# FPGA.net
KiCad netlist of a schematic drawn in Altium Designer
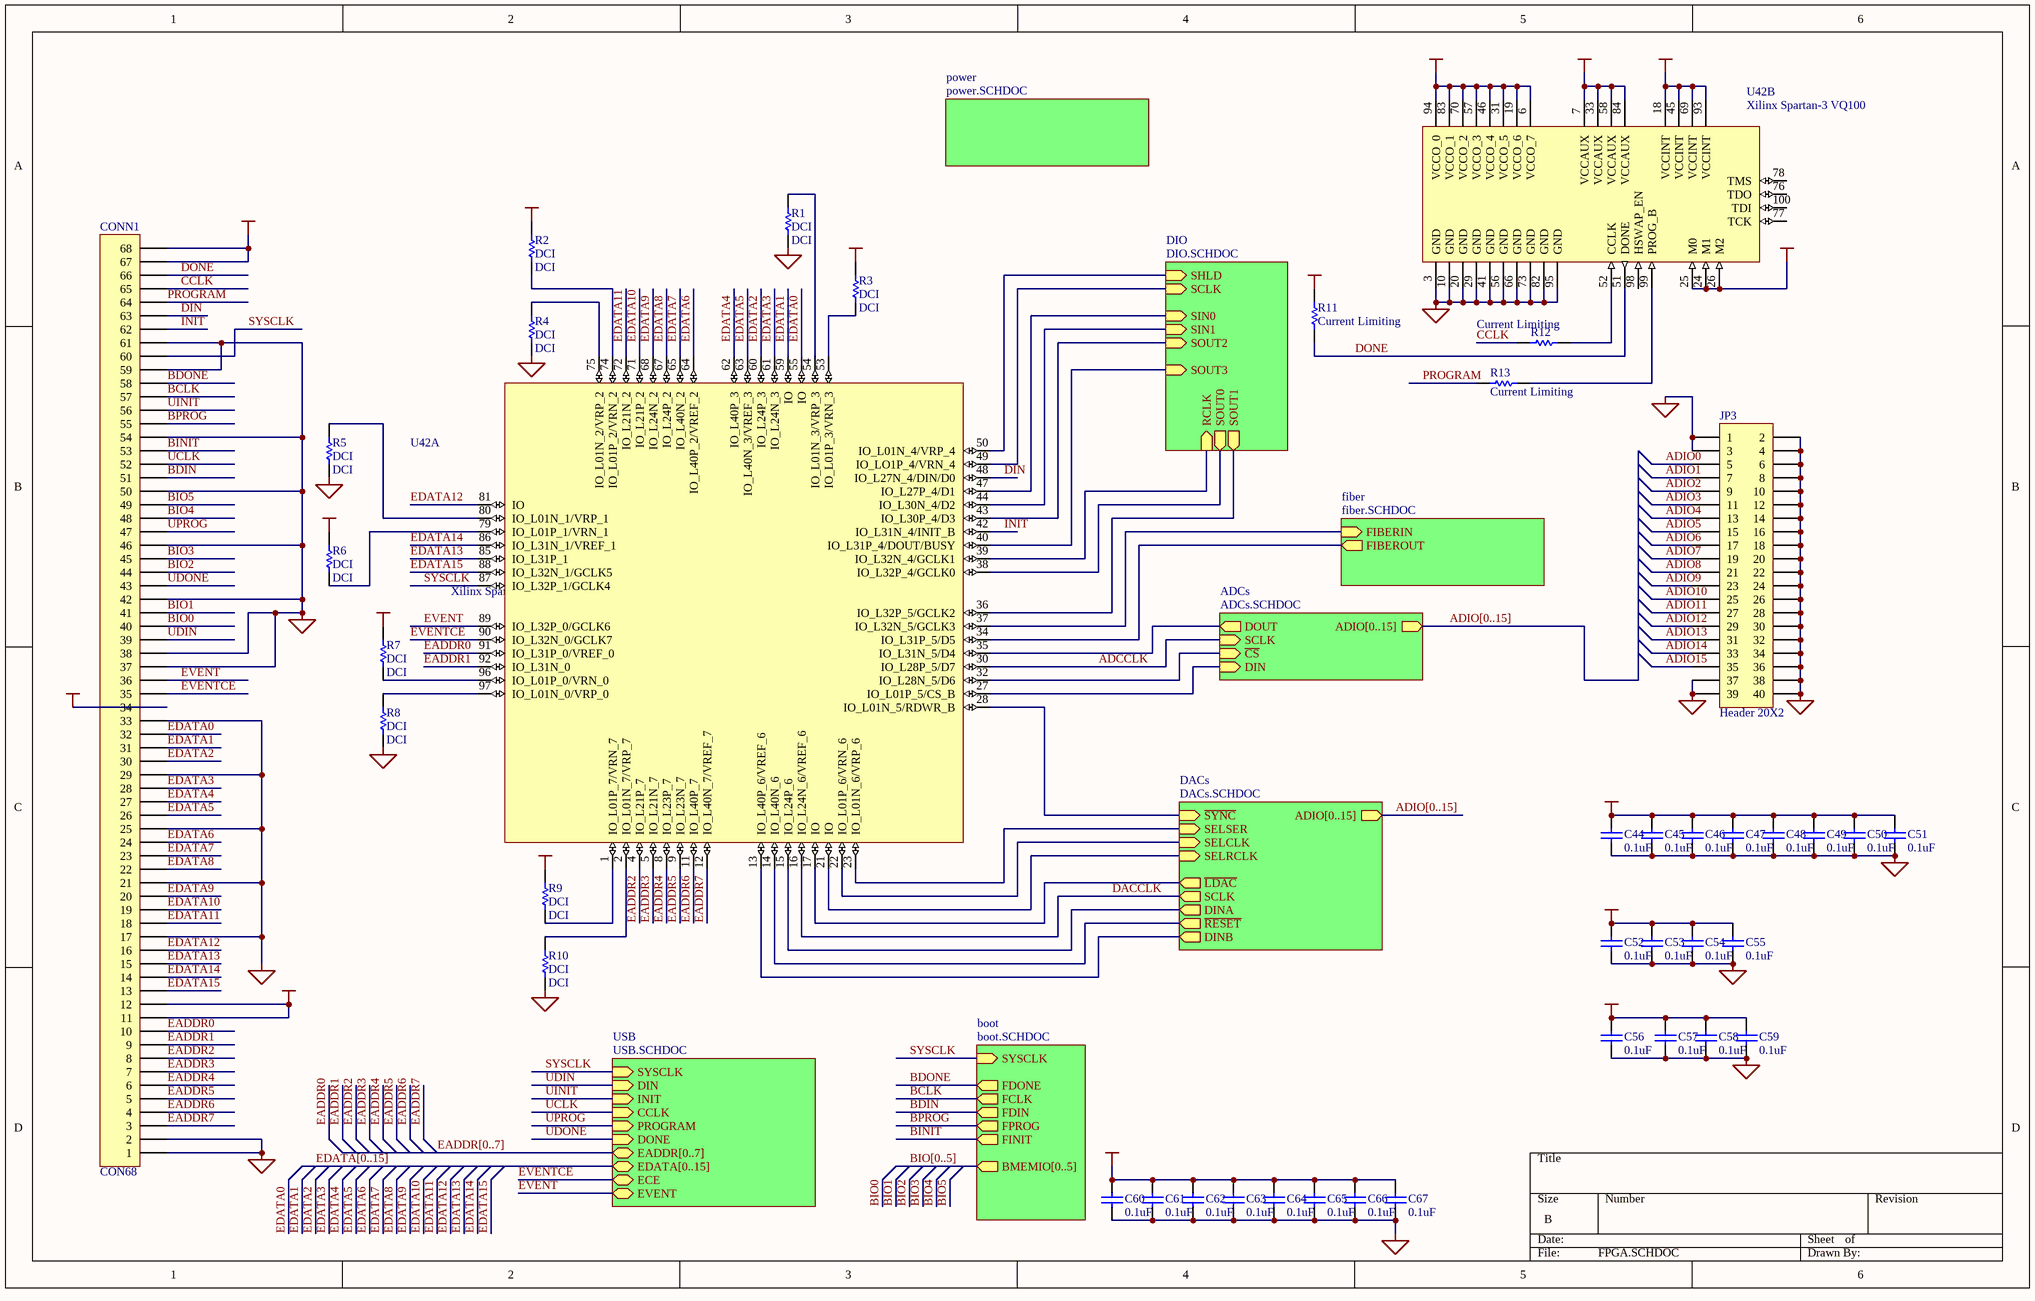
[diagram p0: FPGA.SCHDOC]

(export (version "E")
  (design (tool "Eeschema 10.0.6"))
  (components
    (comp (ref "C44")
      (value "Cap")
      (footprint "CC1608-0603")
      (description "Capacitor")
      (fields
        (field (name "MANUFACTURER") "Generic Components")
        (field (name "ALTIUM_VALUE") "0.1uF")
        (field (name "PUBLISHER") "Altium Limited")
      )
      (libsource (lib "Miscellaneous Devices") (part "Cap"))
    )
    (comp (ref "C45")
      (value "Cap")
      (footprint "CC1608-0603")
      (description "Capacitor")
      (fields
        (field (name "MANUFACTURER") "Generic Components")
        (field (name "ALTIUM_VALUE") "0.1uF")
        (field (name "PUBLISHER") "Altium Limited")
      )
      (libsource (lib "Miscellaneous Devices") (part "Cap"))
    )
    (comp (ref "C46")
      (value "Cap")
      (footprint "CC1608-0603")
      (description "Capacitor")
      (fields
        (field (name "MANUFACTURER") "Generic Components")
        (field (name "ALTIUM_VALUE") "0.1uF")
        (field (name "PUBLISHER") "Altium Limited")
      )
      (libsource (lib "Miscellaneous Devices") (part "Cap"))
    )
    (comp (ref "C47")
      (value "Cap")
      (footprint "CC1608-0603")
      (description "Capacitor")
      (fields
        (field (name "MANUFACTURER") "Generic Components")
        (field (name "ALTIUM_VALUE") "0.1uF")
        (field (name "PUBLISHER") "Altium Limited")
      )
      (libsource (lib "Miscellaneous Devices") (part "Cap"))
    )
    (comp (ref "C48")
      (value "Cap")
      (footprint "CC1608-0603")
      (description "Capacitor")
      (fields
        (field (name "MANUFACTURER") "Generic Components")
        (field (name "ALTIUM_VALUE") "0.1uF")
        (field (name "PUBLISHER") "Altium Limited")
      )
      (libsource (lib "Miscellaneous Devices") (part "Cap"))
    )
    (comp (ref "C49")
      (value "Cap")
      (footprint "CC1608-0603")
      (description "Capacitor")
      (fields
        (field (name "MANUFACTURER") "Generic Components")
        (field (name "ALTIUM_VALUE") "0.1uF")
        (field (name "PUBLISHER") "Altium Limited")
      )
      (libsource (lib "Miscellaneous Devices") (part "Cap"))
    )
    (comp (ref "C50")
      (value "Cap")
      (footprint "CC1608-0603")
      (description "Capacitor")
      (fields
        (field (name "MANUFACTURER") "Generic Components")
        (field (name "ALTIUM_VALUE") "0.1uF")
        (field (name "PUBLISHER") "Altium Limited")
      )
      (libsource (lib "Miscellaneous Devices") (part "Cap"))
    )
    (comp (ref "C51")
      (value "Cap")
      (footprint "CC1608-0603")
      (description "Capacitor")
      (fields
        (field (name "MANUFACTURER") "Generic Components")
        (field (name "ALTIUM_VALUE") "0.1uF")
        (field (name "PUBLISHER") "Altium Limited")
      )
      (libsource (lib "Miscellaneous Devices") (part "Cap"))
    )
    (comp (ref "C52")
      (value "Cap")
      (footprint "CC1608-0603")
      (description "Capacitor")
      (fields
        (field (name "MANUFACTURER") "Generic Components")
        (field (name "ALTIUM_VALUE") "0.1uF")
        (field (name "PUBLISHER") "Altium Limited")
      )
      (libsource (lib "Miscellaneous Devices") (part "Cap"))
    )
    (comp (ref "C53")
      (value "Cap")
      (footprint "CC1608-0603")
      (description "Capacitor")
      (fields
        (field (name "MANUFACTURER") "Generic Components")
        (field (name "ALTIUM_VALUE") "0.1uF")
        (field (name "PUBLISHER") "Altium Limited")
      )
      (libsource (lib "Miscellaneous Devices") (part "Cap"))
    )
    (comp (ref "C54")
      (value "Cap")
      (footprint "CC1608-0603")
      (description "Capacitor")
      (fields
        (field (name "MANUFACTURER") "Generic Components")
        (field (name "ALTIUM_VALUE") "0.1uF")
        (field (name "PUBLISHER") "Altium Limited")
      )
      (libsource (lib "Miscellaneous Devices") (part "Cap"))
    )
    (comp (ref "C55")
      (value "Cap")
      (footprint "CC1608-0603")
      (description "Capacitor")
      (fields
        (field (name "MANUFACTURER") "Generic Components")
        (field (name "ALTIUM_VALUE") "0.1uF")
        (field (name "PUBLISHER") "Altium Limited")
      )
      (libsource (lib "Miscellaneous Devices") (part "Cap"))
    )
    (comp (ref "C56")
      (value "Cap")
      (footprint "CC1608-0603")
      (description "Capacitor")
      (fields
        (field (name "MANUFACTURER") "Generic Components")
        (field (name "ALTIUM_VALUE") "0.1uF")
        (field (name "PUBLISHER") "Altium Limited")
      )
      (libsource (lib "Miscellaneous Devices") (part "Cap"))
    )
    (comp (ref "C57")
      (value "Cap")
      (footprint "CC1608-0603")
      (description "Capacitor")
      (fields
        (field (name "MANUFACTURER") "Generic Components")
        (field (name "ALTIUM_VALUE") "0.1uF")
        (field (name "PUBLISHER") "Altium Limited")
      )
      (libsource (lib "Miscellaneous Devices") (part "Cap"))
    )
    (comp (ref "C58")
      (value "Cap")
      (footprint "CC1608-0603")
      (description "Capacitor")
      (fields
        (field (name "MANUFACTURER") "Generic Components")
        (field (name "ALTIUM_VALUE") "0.1uF")
        (field (name "PUBLISHER") "Altium Limited")
      )
      (libsource (lib "Miscellaneous Devices") (part "Cap"))
    )
    (comp (ref "C59")
      (value "Cap")
      (footprint "CC1608-0603")
      (description "Capacitor")
      (fields
        (field (name "MANUFACTURER") "Generic Components")
        (field (name "ALTIUM_VALUE") "0.1uF")
        (field (name "PUBLISHER") "Altium Limited")
      )
      (libsource (lib "Miscellaneous Devices") (part "Cap"))
    )
    (comp (ref "C60")
      (value "Cap")
      (footprint "CC1608-0603")
      (description "Capacitor")
      (fields
        (field (name "MANUFACTURER") "Generic Components")
        (field (name "ALTIUM_VALUE") "0.1uF")
        (field (name "PUBLISHER") "Altium Limited")
      )
      (libsource (lib "Miscellaneous Devices") (part "Cap"))
    )
    (comp (ref "C61")
      (value "Cap")
      (footprint "CC1608-0603")
      (description "Capacitor")
      (fields
        (field (name "MANUFACTURER") "Generic Components")
        (field (name "ALTIUM_VALUE") "0.1uF")
        (field (name "PUBLISHER") "Altium Limited")
      )
      (libsource (lib "Miscellaneous Devices") (part "Cap"))
    )
    (comp (ref "C62")
      (value "Cap")
      (footprint "CC1608-0603")
      (description "Capacitor")
      (fields
        (field (name "MANUFACTURER") "Generic Components")
        (field (name "ALTIUM_VALUE") "0.1uF")
        (field (name "PUBLISHER") "Altium Limited")
      )
      (libsource (lib "Miscellaneous Devices") (part "Cap"))
    )
    (comp (ref "C63")
      (value "Cap")
      (footprint "CC1608-0603")
      (description "Capacitor")
      (fields
        (field (name "MANUFACTURER") "Generic Components")
        (field (name "ALTIUM_VALUE") "0.1uF")
        (field (name "PUBLISHER") "Altium Limited")
      )
      (libsource (lib "Miscellaneous Devices") (part "Cap"))
    )
    (comp (ref "C64")
      (value "Cap")
      (footprint "CC1608-0603")
      (description "Capacitor")
      (fields
        (field (name "MANUFACTURER") "Generic Components")
        (field (name "ALTIUM_VALUE") "0.1uF")
        (field (name "PUBLISHER") "Altium Limited")
      )
      (libsource (lib "Miscellaneous Devices") (part "Cap"))
    )
    (comp (ref "C65")
      (value "Cap")
      (footprint "CC1608-0603")
      (description "Capacitor")
      (fields
        (field (name "MANUFACTURER") "Generic Components")
        (field (name "ALTIUM_VALUE") "0.1uF")
        (field (name "PUBLISHER") "Altium Limited")
      )
      (libsource (lib "Miscellaneous Devices") (part "Cap"))
    )
    (comp (ref "C66")
      (value "Cap")
      (footprint "CC1608-0603")
      (description "Capacitor")
      (fields
        (field (name "MANUFACTURER") "Generic Components")
        (field (name "ALTIUM_VALUE") "0.1uF")
        (field (name "PUBLISHER") "Altium Limited")
      )
      (libsource (lib "Miscellaneous Devices") (part "Cap"))
    )
    (comp (ref "C67")
      (value "Cap")
      (footprint "CC1608-0603")
      (description "Capacitor")
      (fields
        (field (name "MANUFACTURER") "Generic Components")
        (field (name "ALTIUM_VALUE") "0.1uF")
        (field (name "PUBLISHER") "Altium Limited")
      )
      (libsource (lib "Miscellaneous Devices") (part "Cap"))
    )
    (comp (ref "CONN1")
      (value "CON68")
      (footprint "my packages:MOLEX 71661-2068")
      (libsource (lib "My devices") (part "CON68"))
    )
    (comp (ref "JP3")
      (value "Header 20X2")
      (footprint "HDR2X20")
      (description "Header, 20-Pin, Dual row")
      (fields (field (name "MANUFACTURER") "Generic Components") (field (name "PUBLISHER") "Altium Limited"))
      (libsource (lib "Miscellaneous Connectors") (part "Header 20X2"))
    )
    (comp (ref "R1")
      (value "DCI")
      (footprint "CC1608-0603")
      (description "Resistor")
      (fields
        (field (name "MANUFACTURER") "Generic Components")
        (field (name "ALTIUM_VALUE") "DCI")
        (field (name "PUBLISHER") "Altium Limited")
      )
      (libsource (lib "Miscellaneous Devices") (part "Res1"))
    )
    (comp (ref "R2")
      (value "DCI")
      (footprint "CC1608-0603")
      (description "Resistor")
      (fields
        (field (name "MANUFACTURER") "Generic Components")
        (field (name "ALTIUM_VALUE") "DCI")
        (field (name "PUBLISHER") "Altium Limited")
      )
      (libsource (lib "Miscellaneous Devices") (part "Res1"))
    )
    (comp (ref "R3")
      (value "DCI")
      (footprint "CC1608-0603")
      (description "Resistor")
      (fields
        (field (name "MANUFACTURER") "Generic Components")
        (field (name "ALTIUM_VALUE") "DCI")
        (field (name "PUBLISHER") "Altium Limited")
      )
      (libsource (lib "Miscellaneous Devices") (part "Res1"))
    )
    (comp (ref "R4")
      (value "DCI")
      (footprint "CC1608-0603")
      (description "Resistor")
      (fields
        (field (name "MANUFACTURER") "Generic Components")
        (field (name "ALTIUM_VALUE") "DCI")
        (field (name "PUBLISHER") "Altium Limited")
      )
      (libsource (lib "Miscellaneous Devices") (part "Res1"))
    )
    (comp (ref "R5")
      (value "DCI")
      (footprint "CC1608-0603")
      (description "Resistor")
      (fields
        (field (name "MANUFACTURER") "Generic Components")
        (field (name "ALTIUM_VALUE") "DCI")
        (field (name "PUBLISHER") "Altium Limited")
      )
      (libsource (lib "Miscellaneous Devices") (part "Res1"))
    )
    (comp (ref "R6")
      (value "DCI")
      (footprint "CC1608-0603")
      (description "Resistor")
      (fields
        (field (name "MANUFACTURER") "Generic Components")
        (field (name "ALTIUM_VALUE") "DCI")
        (field (name "PUBLISHER") "Altium Limited")
      )
      (libsource (lib "Miscellaneous Devices") (part "Res1"))
    )
    (comp (ref "R7")
      (value "DCI")
      (footprint "CC1608-0603")
      (description "Resistor")
      (fields
        (field (name "MANUFACTURER") "Generic Components")
        (field (name "ALTIUM_VALUE") "DCI")
        (field (name "PUBLISHER") "Altium Limited")
      )
      (libsource (lib "Miscellaneous Devices") (part "Res1"))
    )
    (comp (ref "R8")
      (value "DCI")
      (footprint "CC1608-0603")
      (description "Resistor")
      (fields
        (field (name "MANUFACTURER") "Generic Components")
        (field (name "ALTIUM_VALUE") "DCI")
        (field (name "PUBLISHER") "Altium Limited")
      )
      (libsource (lib "Miscellaneous Devices") (part "Res1"))
    )
    (comp (ref "R9")
      (value "DCI")
      (footprint "CC1608-0603")
      (description "Resistor")
      (fields
        (field (name "MANUFACTURER") "Generic Components")
        (field (name "ALTIUM_VALUE") "DCI")
        (field (name "PUBLISHER") "Altium Limited")
      )
      (libsource (lib "Miscellaneous Devices") (part "Res1"))
    )
    (comp (ref "R10")
      (value "DCI")
      (footprint "CC1608-0603")
      (description "Resistor")
      (fields
        (field (name "MANUFACTURER") "Generic Components")
        (field (name "ALTIUM_VALUE") "DCI")
        (field (name "PUBLISHER") "Altium Limited")
      )
      (libsource (lib "Miscellaneous Devices") (part "Res1"))
    )
    (comp (ref "R11")
      (value "Current Limiting")
      (footprint "CC1608-0603")
      (description "Resistor")
      (fields (field (name "MANUFACTURER") "Generic Components") (field (name "PUBLISHER") "Altium Limited"))
      (libsource (lib "Miscellaneous Devices") (part "Res1"))
    )
    (comp (ref "R12")
      (value "Current Limiting")
      (footprint "CC1608-0603")
      (description "Resistor")
      (fields (field (name "MANUFACTURER") "Generic Components") (field (name "PUBLISHER") "Altium Limited"))
      (libsource (lib "Miscellaneous Devices") (part "Res1"))
    )
    (comp (ref "R13")
      (value "Current Limiting")
      (footprint "CC1608-0603")
      (description "Resistor")
      (fields (field (name "MANUFACTURER") "Generic Components") (field (name "PUBLISHER") "Altium Limited"))
      (libsource (lib "Miscellaneous Devices") (part "Res1"))
    )
    (comp (ref "U42")
      (value "Xilinx Spartan-3 VQ100")
      (footprint "F-QFP14X14-G100/N")
      (libsource (lib "My devices") (part "XC3S50-VQ100"))
    )
  )
  (nets
    (net (code "1") (name "+1.2VCC") (class "Default")
      (node (ref "C52") (pin "1") (pinfunction "1_1") (pintype "passive"))
      (node (ref "C53") (pin "1") (pinfunction "1_1") (pintype "passive"))
      (node (ref "C54") (pin "1") (pinfunction "1_1") (pintype "passive"))
      (node (ref "C55") (pin "1") (pinfunction "1_1") (pintype "passive"))
      (node (ref "U42") (pin "18") (pinfunction "VCCINT_18") (pintype "power_in"))
      (node (ref "U42") (pin "45") (pinfunction "VCCINT_45") (pintype "power_in"))
      (node (ref "U42") (pin "69") (pinfunction "VCCINT_69") (pintype "power_in"))
      (node (ref "U42") (pin "93") (pinfunction "VCCINT_93") (pintype "power_in"))
    )
    (net (code "2") (name "+2.5VCC") (class "Default")
      (node (ref "C56") (pin "1") (pinfunction "1_1") (pintype "passive"))
      (node (ref "C57") (pin "1") (pinfunction "1_1") (pintype "passive"))
      (node (ref "C58") (pin "1") (pinfunction "1_1") (pintype "passive"))
      (node (ref "C59") (pin "1") (pinfunction "1_1") (pintype "passive"))
      (node (ref "U42") (pin "33") (pinfunction "VCCAUX_33") (pintype "power_in"))
      (node (ref "U42") (pin "58") (pinfunction "VCCAUX_58") (pintype "power_in"))
      (node (ref "U42") (pin "7") (pinfunction "VCCAUX_7") (pintype "power_in"))
      (node (ref "U42") (pin "84") (pinfunction "VCCAUX_84") (pintype "power_in"))
    )
    (net (code "3") (name "+5VCC") (class "Default")
      (node (ref "C60") (pin "2") (pinfunction "2_2") (pintype "passive"))
      (node (ref "C61") (pin "2") (pinfunction "2_2") (pintype "passive"))
      (node (ref "C62") (pin "2") (pinfunction "2_2") (pintype "passive"))
      (node (ref "C63") (pin "2") (pinfunction "2_2") (pintype "passive"))
      (node (ref "C64") (pin "2") (pinfunction "2_2") (pintype "passive"))
      (node (ref "C65") (pin "2") (pinfunction "2_2") (pintype "passive"))
      (node (ref "C66") (pin "2") (pinfunction "2_2") (pintype "passive"))
      (node (ref "C67") (pin "2") (pinfunction "2_2") (pintype "passive"))
      (node (ref "CONN1") (pin "34") (pinfunction "34_34") (pintype "passive"))
    )
    (net (code "4") (name "/ADCCLK") (class "Default")
      (node (ref "U42") (pin "30") (pinfunction "IO_L28P_5/D7_30") (pintype "bidirectional"))
    )
    (net (code "5") (name "/ADIO0") (class "Default")
      (node (ref "JP3") (pin "5") (pinfunction "5_5") (pintype "passive"))
    )
    (net (code "6") (name "/ADIO1") (class "Default")
      (node (ref "JP3") (pin "7") (pinfunction "7_7") (pintype "passive"))
    )
    (net (code "7") (name "/ADIO2") (class "Default")
      (node (ref "JP3") (pin "9") (pinfunction "9_9") (pintype "passive"))
    )
    (net (code "8") (name "/ADIO3") (class "Default")
      (node (ref "JP3") (pin "11") (pinfunction "11_11") (pintype "passive"))
    )
    (net (code "9") (name "/ADIO4") (class "Default")
      (node (ref "JP3") (pin "13") (pinfunction "13_13") (pintype "passive"))
    )
    (net (code "10") (name "/ADIO5") (class "Default")
      (node (ref "JP3") (pin "15") (pinfunction "15_15") (pintype "passive"))
    )
    (net (code "11") (name "/ADIO6") (class "Default")
      (node (ref "JP3") (pin "17") (pinfunction "17_17") (pintype "passive"))
    )
    (net (code "12") (name "/ADIO7") (class "Default")
      (node (ref "JP3") (pin "19") (pinfunction "19_19") (pintype "passive"))
    )
    (net (code "13") (name "/ADIO8") (class "Default")
      (node (ref "JP3") (pin "21") (pinfunction "21_21") (pintype "passive"))
    )
    (net (code "14") (name "/ADIO9") (class "Default")
      (node (ref "JP3") (pin "23") (pinfunction "23_23") (pintype "passive"))
    )
    (net (code "15") (name "/ADIO10") (class "Default")
      (node (ref "JP3") (pin "25") (pinfunction "25_25") (pintype "passive"))
    )
    (net (code "16") (name "/ADIO11") (class "Default")
      (node (ref "JP3") (pin "27") (pinfunction "27_27") (pintype "passive"))
    )
    (net (code "17") (name "/ADIO12") (class "Default")
      (node (ref "JP3") (pin "29") (pinfunction "29_29") (pintype "passive"))
    )
    (net (code "18") (name "/ADIO13") (class "Default")
      (node (ref "JP3") (pin "31") (pinfunction "31_31") (pintype "passive"))
    )
    (net (code "19") (name "/ADIO14") (class "Default")
      (node (ref "JP3") (pin "33") (pinfunction "33_33") (pintype "passive"))
    )
    (net (code "20") (name "/ADIO15") (class "Default")
      (node (ref "JP3") (pin "35") (pinfunction "35_35") (pintype "passive"))
    )
    (net (code "22") (name "/BCLK") (class "Default")
      (node (ref "CONN1") (pin "57") (pinfunction "57_57") (pintype "passive"))
    )
    (net (code "23") (name "/BDIN") (class "Default")
      (node (ref "CONN1") (pin "51") (pinfunction "51_51") (pintype "passive"))
    )
    (net (code "24") (name "/BDONE") (class "Default")
      (node (ref "CONN1") (pin "58") (pinfunction "58_58") (pintype "passive"))
    )
    (net (code "25") (name "/BINIT") (class "Default")
      (node (ref "CONN1") (pin "53") (pinfunction "53_53") (pintype "passive"))
    )
    (net (code "26") (name "/BIO0") (class "Default")
      (node (ref "CONN1") (pin "40") (pinfunction "40_40") (pintype "passive"))
    )
    (net (code "27") (name "/BIO1") (class "Default")
      (node (ref "CONN1") (pin "41") (pinfunction "41_41") (pintype "passive"))
    )
    (net (code "28") (name "/BIO2") (class "Default")
      (node (ref "CONN1") (pin "44") (pinfunction "44_44") (pintype "passive"))
    )
    (net (code "29") (name "/BIO3") (class "Default")
      (node (ref "CONN1") (pin "45") (pinfunction "45_45") (pintype "passive"))
    )
    (net (code "30") (name "/BIO4") (class "Default")
      (node (ref "CONN1") (pin "48") (pinfunction "48_48") (pintype "passive"))
    )
    (net (code "31") (name "/BIO5") (class "Default")
      (node (ref "CONN1") (pin "49") (pinfunction "49_49") (pintype "passive"))
    )
    (net (code "33") (name "/BPROG") (class "Default")
      (node (ref "CONN1") (pin "55") (pinfunction "55_55") (pintype "passive"))
    )
    (net (code "34") (name "/CCLK") (class "Default")
      (node (ref "CONN1") (pin "65") (pinfunction "65_65") (pintype "passive"))
      (node (ref "R12") (pin "1") (pinfunction "1_1") (pintype "passive"))
    )
    (net (code "35") (name "/DACCLK") (class "Default")
      (node (ref "U42") (pin "16") (pinfunction "IO_L24N_6/VREF_6_16") (pintype "bidirectional"))
    )
    (net (code "36") (name "/DIN") (class "Default")
      (node (ref "CONN1") (pin "63") (pinfunction "63_63") (pintype "passive"))
      (node (ref "U42") (pin "48") (pinfunction "IO_L27N_4/DIN/D0_48") (pintype "bidirectional"))
    )
    (net (code "37") (name "/DINA") (class "Default")
      (node (ref "U42") (pin "15") (pinfunction "IO_L24P_6_15") (pintype "bidirectional"))
    )
    (net (code "38") (name "/DINB") (class "Default")
      (node (ref "U42") (pin "13") (pinfunction "IO_L40P_6/VREF_6_13") (pintype "bidirectional"))
    )
    (net (code "39") (name "/DIN_1") (class "Default")
      (node (ref "U42") (pin "27") (pinfunction "IO_L01P_5/CS_B_27") (pintype "bidirectional"))
    )
    (net (code "40") (name "/DONE") (class "Default")
      (node (ref "CONN1") (pin "66") (pinfunction "66_66") (pintype "passive"))
      (node (ref "R11") (pin "1") (pinfunction "1_1") (pintype "passive"))
      (node (ref "U42") (pin "51") (pinfunction "DONE_51") (pintype "output"))
    )
    (net (code "41") (name "/DOUT") (class "Default")
      (node (ref "U42") (pin "35") (pinfunction "IO_L31N_5/D4_35") (pintype "bidirectional"))
    )
    (net (code "42") (name "/EADDR0") (class "Default")
      (node (ref "CONN1") (pin "10") (pinfunction "10_10") (pintype "passive"))
      (node (ref "U42") (pin "91") (pinfunction "IO_L31P_0/VREF_0_91") (pintype "bidirectional"))
    )
    (net (code "43") (name "/EADDR1") (class "Default")
      (node (ref "CONN1") (pin "9") (pinfunction "9_9") (pintype "passive"))
      (node (ref "U42") (pin "92") (pinfunction "IO_L31N_0_92") (pintype "bidirectional"))
    )
    (net (code "44") (name "/EADDR2") (class "Default")
      (node (ref "CONN1") (pin "8") (pinfunction "8_8") (pintype "passive"))
      (node (ref "U42") (pin "4") (pinfunction "IO_L21P_7_4") (pintype "bidirectional"))
    )
    (net (code "45") (name "/EADDR3") (class "Default")
      (node (ref "CONN1") (pin "7") (pinfunction "7_7") (pintype "passive"))
      (node (ref "U42") (pin "5") (pinfunction "IO_L21N_7_5") (pintype "bidirectional"))
    )
    (net (code "46") (name "/EADDR4") (class "Default")
      (node (ref "CONN1") (pin "6") (pinfunction "6_6") (pintype "passive"))
      (node (ref "U42") (pin "8") (pinfunction "IO_L23P_7_8") (pintype "bidirectional"))
    )
    (net (code "47") (name "/EADDR5") (class "Default")
      (node (ref "CONN1") (pin "5") (pinfunction "5_5") (pintype "passive"))
      (node (ref "U42") (pin "9") (pinfunction "IO_L23N_7_9") (pintype "bidirectional"))
    )
    (net (code "48") (name "/EADDR6") (class "Default")
      (node (ref "CONN1") (pin "4") (pinfunction "4_4") (pintype "passive"))
      (node (ref "U42") (pin "11") (pinfunction "IO_L40P_7_11") (pintype "bidirectional"))
    )
    (net (code "49") (name "/EADDR7") (class "Default")
      (node (ref "CONN1") (pin "3") (pinfunction "3_3") (pintype "passive"))
      (node (ref "U42") (pin "12") (pinfunction "IO_L40N_7/VREF_7_12") (pintype "bidirectional"))
    )
    (net (code "51") (name "/EDATA0") (class "Default")
      (node (ref "CONN1") (pin "32") (pinfunction "32_32") (pintype "passive"))
      (node (ref "U42") (pin "55") (pinfunction "IO_55") (pintype "bidirectional"))
    )
    (net (code "52") (name "/EDATA1") (class "Default")
      (node (ref "CONN1") (pin "31") (pinfunction "31_31") (pintype "passive"))
      (node (ref "U42") (pin "59") (pinfunction "IO_59") (pintype "bidirectional"))
    )
    (net (code "53") (name "/EDATA2") (class "Default")
      (node (ref "CONN1") (pin "30") (pinfunction "30_30") (pintype "passive"))
      (node (ref "U42") (pin "60") (pinfunction "IO_L24P_3_60") (pintype "bidirectional"))
    )
    (net (code "54") (name "/EDATA3") (class "Default")
      (node (ref "CONN1") (pin "28") (pinfunction "28_28") (pintype "passive"))
      (node (ref "U42") (pin "61") (pinfunction "IO_L24N_3_61") (pintype "bidirectional"))
    )
    (net (code "55") (name "/EDATA4") (class "Default")
      (node (ref "CONN1") (pin "27") (pinfunction "27_27") (pintype "passive"))
      (node (ref "U42") (pin "62") (pinfunction "IO_L40P_3_62") (pintype "bidirectional"))
    )
    (net (code "56") (name "/EDATA5") (class "Default")
      (node (ref "CONN1") (pin "26") (pinfunction "26_26") (pintype "passive"))
      (node (ref "U42") (pin "63") (pinfunction "IO_L40N_3/VREF_3_63") (pintype "bidirectional"))
    )
    (net (code "57") (name "/EDATA6") (class "Default")
      (node (ref "CONN1") (pin "24") (pinfunction "24_24") (pintype "passive"))
      (node (ref "U42") (pin "64") (pinfunction "IO_L40P_2/VREF_2_64") (pintype "bidirectional"))
    )
    (net (code "58") (name "/EDATA7") (class "Default")
      (node (ref "CONN1") (pin "23") (pinfunction "23_23") (pintype "passive"))
      (node (ref "U42") (pin "65") (pinfunction "IO_L40N_2_65") (pintype "bidirectional"))
    )
    (net (code "59") (name "/EDATA8") (class "Default")
      (node (ref "CONN1") (pin "22") (pinfunction "22_22") (pintype "passive"))
      (node (ref "U42") (pin "67") (pinfunction "IO_L24P_2_67") (pintype "bidirectional"))
    )
    (net (code "60") (name "/EDATA9") (class "Default")
      (node (ref "CONN1") (pin "20") (pinfunction "20_20") (pintype "passive"))
      (node (ref "U42") (pin "68") (pinfunction "IO_L24N_2_68") (pintype "bidirectional"))
    )
    (net (code "61") (name "/EDATA10") (class "Default")
      (node (ref "CONN1") (pin "19") (pinfunction "19_19") (pintype "passive"))
      (node (ref "U42") (pin "71") (pinfunction "IO_L21P_2_71") (pintype "bidirectional"))
    )
    (net (code "62") (name "/EDATA11") (class "Default")
      (node (ref "CONN1") (pin "18") (pinfunction "18_18") (pintype "passive"))
      (node (ref "U42") (pin "72") (pinfunction "IO_L21N_2_72") (pintype "bidirectional"))
    )
    (net (code "63") (name "/EDATA12") (class "Default")
      (node (ref "CONN1") (pin "16") (pinfunction "16_16") (pintype "passive"))
      (node (ref "U42") (pin "81") (pinfunction "IO_81") (pintype "bidirectional"))
    )
    (net (code "64") (name "/EDATA13") (class "Default")
      (node (ref "CONN1") (pin "15") (pinfunction "15_15") (pintype "passive"))
      (node (ref "U42") (pin "85") (pinfunction "IO_L31P_1_85") (pintype "bidirectional"))
    )
    (net (code "65") (name "/EDATA14") (class "Default")
      (node (ref "CONN1") (pin "14") (pinfunction "14_14") (pintype "passive"))
      (node (ref "U42") (pin "86") (pinfunction "IO_L31N_1/VREF_1_86") (pintype "bidirectional"))
    )
    (net (code "66") (name "/EDATA15") (class "Default")
      (node (ref "CONN1") (pin "13") (pinfunction "13_13") (pintype "passive"))
      (node (ref "U42") (pin "88") (pinfunction "IO_L32N_1/GCLK5_88") (pintype "bidirectional"))
    )
    (net (code "68") (name "/EVENT") (class "Default")
      (node (ref "CONN1") (pin "36") (pinfunction "36_36") (pintype "passive"))
      (node (ref "U42") (pin "89") (pinfunction "IO_L32P_0/GCLK6_89") (pintype "bidirectional"))
    )
    (net (code "69") (name "/EVENTCE") (class "Default")
      (node (ref "CONN1") (pin "35") (pinfunction "35_35") (pintype "passive"))
      (node (ref "U42") (pin "90") (pinfunction "IO_L32N_0/GCLK7_90") (pintype "bidirectional"))
    )
    (net (code "70") (name "/FIBERIN") (class "Default")
      (node (ref "U42") (pin "37") (pinfunction "IO_L32N_5/GCLK3_37") (pintype "bidirectional"))
    )
    (net (code "71") (name "/FIBEROUT") (class "Default")
      (node (ref "U42") (pin "34") (pinfunction "IO_L31P_5/D5_34") (pintype "bidirectional"))
    )
    (net (code "72") (name "/INIT") (class "Default")
      (node (ref "CONN1") (pin "62") (pinfunction "62_62") (pintype "passive"))
      (node (ref "U42") (pin "42") (pinfunction "IO_L31N_4/INIT_B_42") (pintype "bidirectional"))
    )
    (net (code "73") (name "/PROGRAM") (class "Default")
      (node (ref "CONN1") (pin "64") (pinfunction "64_64") (pintype "passive"))
      (node (ref "R13") (pin "1") (pinfunction "1_1") (pintype "passive"))
    )
    (net (code "74") (name "/RCLK") (class "Default")
      (node (ref "U42") (pin "39") (pinfunction "IO_L32N_4/GCLK1_39") (pintype "bidirectional"))
    )
    (net (code "75") (name "/SCLK") (class "Default")
      (node (ref "U42") (pin "49") (pinfunction "IO_LO1P_4/VRN_4_49") (pintype "bidirectional"))
    )
    (net (code "76") (name "/SELCLK") (class "Default")
      (node (ref "U42") (pin "22") (pinfunction "IO_L01P_6/VRN_6_22") (pintype "bidirectional"))
    )
    (net (code "77") (name "/SELRCLK") (class "Default")
      (node (ref "U42") (pin "21") (pinfunction "IO_21") (pintype "bidirectional"))
    )
    (net (code "78") (name "/SELSER") (class "Default")
      (node (ref "U42") (pin "23") (pinfunction "IO_L01N_6/VRP_6_23") (pintype "bidirectional"))
    )
    (net (code "79") (name "/SHLD") (class "Default")
      (node (ref "U42") (pin "50") (pinfunction "IO_L01N_4/VRP_4_50") (pintype "bidirectional"))
    )
    (net (code "80") (name "/SIN0") (class "Default")
      (node (ref "U42") (pin "47") (pinfunction "IO_L27P_4/D1_47") (pintype "bidirectional"))
    )
    (net (code "81") (name "/SIN1") (class "Default")
      (node (ref "U42") (pin "44") (pinfunction "IO_L30N_4/D2_44") (pintype "bidirectional"))
    )
    (net (code "82") (name "/SOUT0") (class "Default")
      (node (ref "U42") (pin "38") (pinfunction "IO_L32P_4/GCLK0_38") (pintype "bidirectional"))
    )
    (net (code "83") (name "/SOUT1") (class "Default")
      (node (ref "U42") (pin "36") (pinfunction "IO_L32P_5/GCLK2_36") (pintype "bidirectional"))
    )
    (net (code "84") (name "/SOUT2") (class "Default")
      (node (ref "U42") (pin "43") (pinfunction "IO_L30P_4/D3_43") (pintype "bidirectional"))
    )
    (net (code "85") (name "/SOUT3") (class "Default")
      (node (ref "U42") (pin "40") (pinfunction "IO_L31P_4/DOUT/BUSY_40") (pintype "bidirectional"))
    )
    (net (code "86") (name "/SYSCLK") (class "Default")
      (node (ref "CONN1") (pin "60") (pinfunction "60_60") (pintype "passive"))
      (node (ref "U42") (pin "87") (pinfunction "IO_L32P_1/GCLK4_87") (pintype "bidirectional"))
    )
    (net (code "87") (name "/UCLK") (class "Default")
      (node (ref "CONN1") (pin "52") (pinfunction "52_52") (pintype "passive"))
    )
    (net (code "88") (name "/UDIN") (class "Default")
      (node (ref "CONN1") (pin "39") (pinfunction "39_39") (pintype "passive"))
    )
    (net (code "89") (name "/UDONE") (class "Default")
      (node (ref "CONN1") (pin "43") (pinfunction "43_43") (pintype "passive"))
    )
    (net (code "90") (name "/UINIT") (class "Default")
      (node (ref "CONN1") (pin "56") (pinfunction "56_56") (pintype "passive"))
    )
    (net (code "91") (name "/UPROG") (class "Default")
      (node (ref "CONN1") (pin "47") (pinfunction "47_47") (pintype "passive"))
    )
    (net (code "92") (name "/~{CS}") (class "Default")
      (node (ref "U42") (pin "32") (pinfunction "IO_L28N_5/D6_32") (pintype "bidirectional"))
    )
    (net (code "93") (name "/~{LDAC}") (class "Default")
      (node (ref "U42") (pin "17") (pinfunction "IO_17") (pintype "bidirectional"))
    )
    (net (code "94") (name "/~{RESET}") (class "Default")
      (node (ref "U42") (pin "14") (pinfunction "IO_L40N_6_14") (pintype "bidirectional"))
    )
    (net (code "95") (name "/~{SYNC}") (class "Default")
      (node (ref "U42") (pin "28") (pinfunction "IO_L01N_5/RDWR_B_28") (pintype "bidirectional"))
    )
    (net (code "96") (name "GND") (class "Default")
      (node (ref "C44") (pin "2") (pinfunction "2_2") (pintype "passive"))
      (node (ref "C45") (pin "2") (pinfunction "2_2") (pintype "passive"))
      (node (ref "C46") (pin "2") (pinfunction "2_2") (pintype "passive"))
      (node (ref "C47") (pin "2") (pinfunction "2_2") (pintype "passive"))
      (node (ref "C48") (pin "2") (pinfunction "2_2") (pintype "passive"))
      (node (ref "C49") (pin "2") (pinfunction "2_2") (pintype "passive"))
      (node (ref "C50") (pin "2") (pinfunction "2_2") (pintype "passive"))
      (node (ref "C51") (pin "2") (pinfunction "2_2") (pintype "passive"))
      (node (ref "C52") (pin "2") (pinfunction "2_2") (pintype "passive"))
      (node (ref "C53") (pin "2") (pinfunction "2_2") (pintype "passive"))
      (node (ref "C54") (pin "2") (pinfunction "2_2") (pintype "passive"))
      (node (ref "C55") (pin "2") (pinfunction "2_2") (pintype "passive"))
      (node (ref "C56") (pin "2") (pinfunction "2_2") (pintype "passive"))
      (node (ref "C57") (pin "2") (pinfunction "2_2") (pintype "passive"))
      (node (ref "C58") (pin "2") (pinfunction "2_2") (pintype "passive"))
      (node (ref "C59") (pin "2") (pinfunction "2_2") (pintype "passive"))
      (node (ref "C60") (pin "1") (pinfunction "1_1") (pintype "passive"))
      (node (ref "C61") (pin "1") (pinfunction "1_1") (pintype "passive"))
      (node (ref "C62") (pin "1") (pinfunction "1_1") (pintype "passive"))
      (node (ref "C63") (pin "1") (pinfunction "1_1") (pintype "passive"))
      (node (ref "C64") (pin "1") (pinfunction "1_1") (pintype "passive"))
      (node (ref "C65") (pin "1") (pinfunction "1_1") (pintype "passive"))
      (node (ref "C66") (pin "1") (pinfunction "1_1") (pintype "passive"))
      (node (ref "C67") (pin "1") (pinfunction "1_1") (pintype "passive"))
      (node (ref "CONN1") (pin "1") (pinfunction "1_1") (pintype "passive"))
      (node (ref "CONN1") (pin "17") (pinfunction "17_17") (pintype "passive"))
      (node (ref "CONN1") (pin "2") (pinfunction "2_2") (pintype "passive"))
      (node (ref "CONN1") (pin "21") (pinfunction "21_21") (pintype "passive"))
      (node (ref "CONN1") (pin "25") (pinfunction "25_25") (pintype "passive"))
      (node (ref "CONN1") (pin "29") (pinfunction "29_29") (pintype "passive"))
      (node (ref "CONN1") (pin "33") (pinfunction "33_33") (pintype "passive"))
      (node (ref "CONN1") (pin "37") (pinfunction "37_37") (pintype "passive"))
      (node (ref "CONN1") (pin "38") (pinfunction "38_38") (pintype "passive"))
      (node (ref "CONN1") (pin "42") (pinfunction "42_42") (pintype "passive"))
      (node (ref "CONN1") (pin "46") (pinfunction "46_46") (pintype "passive"))
      (node (ref "CONN1") (pin "50") (pinfunction "50_50") (pintype "passive"))
      (node (ref "CONN1") (pin "54") (pinfunction "54_54") (pintype "passive"))
      (node (ref "CONN1") (pin "59") (pinfunction "59_59") (pintype "passive"))
      (node (ref "CONN1") (pin "61") (pinfunction "61_61") (pintype "passive"))
      (node (ref "JP3") (pin "1") (pinfunction "1_1") (pintype "passive"))
      (node (ref "JP3") (pin "10") (pinfunction "10_10") (pintype "passive"))
      (node (ref "JP3") (pin "12") (pinfunction "12_12") (pintype "passive"))
      (node (ref "JP3") (pin "14") (pinfunction "14_14") (pintype "passive"))
      (node (ref "JP3") (pin "16") (pinfunction "16_16") (pintype "passive"))
      (node (ref "JP3") (pin "18") (pinfunction "18_18") (pintype "passive"))
      (node (ref "JP3") (pin "2") (pinfunction "2_2") (pintype "passive"))
      (node (ref "JP3") (pin "20") (pinfunction "20_20") (pintype "passive"))
      (node (ref "JP3") (pin "22") (pinfunction "22_22") (pintype "passive"))
      (node (ref "JP3") (pin "24") (pinfunction "24_24") (pintype "passive"))
      (node (ref "JP3") (pin "26") (pinfunction "26_26") (pintype "passive"))
      (node (ref "JP3") (pin "28") (pinfunction "28_28") (pintype "passive"))
      (node (ref "JP3") (pin "3") (pinfunction "3_3") (pintype "passive"))
      (node (ref "JP3") (pin "30") (pinfunction "30_30") (pintype "passive"))
      (node (ref "JP3") (pin "32") (pinfunction "32_32") (pintype "passive"))
      (node (ref "JP3") (pin "34") (pinfunction "34_34") (pintype "passive"))
      (node (ref "JP3") (pin "36") (pinfunction "36_36") (pintype "passive"))
      (node (ref "JP3") (pin "37") (pinfunction "37_37") (pintype "passive"))
      (node (ref "JP3") (pin "38") (pinfunction "38_38") (pintype "passive"))
      (node (ref "JP3") (pin "39") (pinfunction "39_39") (pintype "passive"))
      (node (ref "JP3") (pin "4") (pinfunction "4_4") (pintype "passive"))
      (node (ref "JP3") (pin "40") (pinfunction "40_40") (pintype "passive"))
      (node (ref "JP3") (pin "6") (pinfunction "6_6") (pintype "passive"))
      (node (ref "JP3") (pin "8") (pinfunction "8_8") (pintype "passive"))
      (node (ref "R1") (pin "1") (pinfunction "1_1") (pintype "passive"))
      (node (ref "R10") (pin "1") (pinfunction "1_1") (pintype "passive"))
      (node (ref "R4") (pin "1") (pinfunction "1_1") (pintype "passive"))
      (node (ref "R5") (pin "1") (pinfunction "1_1") (pintype "passive"))
      (node (ref "R8") (pin "1") (pinfunction "1_1") (pintype "passive"))
      (node (ref "U42") (pin "10") (pinfunction "GND_10") (pintype "power_in"))
      (node (ref "U42") (pin "20") (pinfunction "GND_20") (pintype "power_in"))
      (node (ref "U42") (pin "29") (pinfunction "GND_29") (pintype "power_in"))
      (node (ref "U42") (pin "3") (pinfunction "GND_3") (pintype "power_in"))
      (node (ref "U42") (pin "41") (pinfunction "GND_41") (pintype "power_in"))
      (node (ref "U42") (pin "56") (pinfunction "GND_56") (pintype "power_in"))
      (node (ref "U42") (pin "66") (pinfunction "GND_66") (pintype "power_in"))
      (node (ref "U42") (pin "73") (pinfunction "GND_73") (pintype "power_in"))
      (node (ref "U42") (pin "82") (pinfunction "GND_82") (pintype "power_in"))
      (node (ref "U42") (pin "95") (pinfunction "GND_95") (pintype "power_in"))
    )
    (net (code "97") (name "Net-(U42A-IO_L01N_0{slash}VRP_0)") (class "Default")
      (node (ref "R8") (pin "2") (pinfunction "2_2") (pintype "passive"))
      (node (ref "U42") (pin "97") (pinfunction "IO_L01N_0/VRP_0_97") (pintype "bidirectional"))
    )
    (net (code "98") (name "Net-(U42A-IO_L01N_1{slash}VRP_1)") (class "Default")
      (node (ref "R5") (pin "2") (pinfunction "2_2") (pintype "passive"))
      (node (ref "U42") (pin "80") (pinfunction "IO_L01N_1/VRP_1_80") (pintype "bidirectional"))
    )
    (net (code "99") (name "Net-(U42A-IO_L01N_2{slash}VRP_2)") (class "Default")
      (node (ref "R4") (pin "2") (pinfunction "2_2") (pintype "passive"))
      (node (ref "U42") (pin "75") (pinfunction "IO_L01N_2/VRP_2_75") (pintype "bidirectional"))
    )
    (net (code "100") (name "Net-(U42A-IO_L01N_3{slash}VRP_3)") (class "Default")
      (node (ref "R1") (pin "2") (pinfunction "2_2") (pintype "passive"))
      (node (ref "U42") (pin "54") (pinfunction "IO_L01N_3/VRP_3_54") (pintype "bidirectional"))
    )
    (net (code "101") (name "Net-(U42A-IO_L01N_7{slash}VRP_7)") (class "Default")
      (node (ref "R10") (pin "2") (pinfunction "2_2") (pintype "passive"))
      (node (ref "U42") (pin "2") (pinfunction "IO_L01N_7/VRP_7_2") (pintype "bidirectional"))
    )
    (net (code "102") (name "Net-(U42A-IO_L01P_0{slash}VRN_0)") (class "Default")
      (node (ref "R7") (pin "1") (pinfunction "1_1") (pintype "passive"))
      (node (ref "U42") (pin "96") (pinfunction "IO_L01P_0/VRN_0_96") (pintype "bidirectional"))
    )
    (net (code "103") (name "Net-(U42A-IO_L01P_1{slash}VRN_1)") (class "Default")
      (node (ref "R6") (pin "1") (pinfunction "1_1") (pintype "passive"))
      (node (ref "U42") (pin "79") (pinfunction "IO_L01P_1/VRN_1_79") (pintype "bidirectional"))
    )
    (net (code "104") (name "Net-(U42A-IO_L01P_2{slash}VRN_2)") (class "Default")
      (node (ref "R2") (pin "1") (pinfunction "1_1") (pintype "passive"))
      (node (ref "U42") (pin "74") (pinfunction "IO_L01P_2/VRN_2_74") (pintype "bidirectional"))
    )
    (net (code "105") (name "Net-(U42A-IO_L01P_3{slash}VRN_3)") (class "Default")
      (node (ref "R3") (pin "1") (pinfunction "1_1") (pintype "passive"))
      (node (ref "U42") (pin "53") (pinfunction "IO_L01P_3/VRN_3_53") (pintype "bidirectional"))
    )
    (net (code "106") (name "Net-(U42A-IO_L01P_7{slash}VRN_7)") (class "Default")
      (node (ref "R9") (pin "1") (pinfunction "1_1") (pintype "passive"))
      (node (ref "U42") (pin "1") (pinfunction "IO_L01P_7/VRN_7_1") (pintype "bidirectional"))
    )
    (net (code "107") (name "Net-(U42B-CCLK)") (class "Default")
      (node (ref "R12") (pin "2") (pinfunction "2_2") (pintype "passive"))
      (node (ref "U42") (pin "52") (pinfunction "CCLK_52") (pintype "input"))
    )
    (net (code "108") (name "Net-(U42B-PROG_B)") (class "Default")
      (node (ref "R13") (pin "2") (pinfunction "2_2") (pintype "passive"))
      (node (ref "U42") (pin "99") (pinfunction "PROG_B_99") (pintype "input"))
    )
    (net (code "109") (name "VCC") (class "Default")
      (node (ref "C44") (pin "1") (pinfunction "1_1") (pintype "passive"))
      (node (ref "C45") (pin "1") (pinfunction "1_1") (pintype "passive"))
      (node (ref "C46") (pin "1") (pinfunction "1_1") (pintype "passive"))
      (node (ref "C47") (pin "1") (pinfunction "1_1") (pintype "passive"))
      (node (ref "C48") (pin "1") (pinfunction "1_1") (pintype "passive"))
      (node (ref "C49") (pin "1") (pinfunction "1_1") (pintype "passive"))
      (node (ref "C50") (pin "1") (pinfunction "1_1") (pintype "passive"))
      (node (ref "C51") (pin "1") (pinfunction "1_1") (pintype "passive"))
      (node (ref "CONN1") (pin "11") (pinfunction "11_11") (pintype "passive"))
      (node (ref "CONN1") (pin "12") (pinfunction "12_12") (pintype "passive"))
      (node (ref "CONN1") (pin "67") (pinfunction "67_67") (pintype "passive"))
      (node (ref "CONN1") (pin "68") (pinfunction "68_68") (pintype "passive"))
      (node (ref "R11") (pin "2") (pinfunction "2_2") (pintype "passive"))
      (node (ref "R2") (pin "2") (pinfunction "2_2") (pintype "passive"))
      (node (ref "R3") (pin "2") (pinfunction "2_2") (pintype "passive"))
      (node (ref "R6") (pin "2") (pinfunction "2_2") (pintype "passive"))
      (node (ref "R7") (pin "2") (pinfunction "2_2") (pintype "passive"))
      (node (ref "R9") (pin "2") (pinfunction "2_2") (pintype "passive"))
      (node (ref "U42") (pin "19") (pinfunction "VCCO_6_19") (pintype "power_in"))
      (node (ref "U42") (pin "24") (pinfunction "M1_24") (pintype "input"))
      (node (ref "U42") (pin "25") (pinfunction "M0_25") (pintype "input"))
      (node (ref "U42") (pin "26") (pinfunction "M2_26") (pintype "input"))
      (node (ref "U42") (pin "31") (pinfunction "VCCO_5_31") (pintype "power_in"))
      (node (ref "U42") (pin "46") (pinfunction "VCCO_4_46") (pintype "power_in"))
      (node (ref "U42") (pin "57") (pinfunction "VCCO_3_57") (pintype "power_in"))
      (node (ref "U42") (pin "6") (pinfunction "VCCO_7_6") (pintype "power_in"))
      (node (ref "U42") (pin "70") (pinfunction "VCCO_2_70") (pintype "power_in"))
      (node (ref "U42") (pin "83") (pinfunction "VCCO_1_83") (pintype "power_in"))
      (node (ref "U42") (pin "94") (pinfunction "VCCO_0_94") (pintype "power_in"))
    )
    (net (code "110") (name "unconnected-(U42B-HSWAP_EN-Pad98)") (class "Default")
      (node (ref "U42") (pin "98") (pinfunction "HSWAP_EN_98") (pintype "input"))
    )
    (net (code "111") (name "unconnected-(U42B-TCK-Pad77)") (class "Default")
      (node (ref "U42") (pin "77") (pinfunction "TCK_77") (pintype "bidirectional"))
    )
    (net (code "112") (name "unconnected-(U42B-TDI-Pad100)") (class "Default")
      (node (ref "U42") (pin "100") (pinfunction "TDI_100") (pintype "bidirectional"))
    )
    (net (code "113") (name "unconnected-(U42B-TDO-Pad76)") (class "Default")
      (node (ref "U42") (pin "76") (pinfunction "TDO_76") (pintype "bidirectional"))
    )
    (net (code "114") (name "unconnected-(U42B-TMS-Pad78)") (class "Default")
      (node (ref "U42") (pin "78") (pinfunction "TMS_78") (pintype "bidirectional"))
    )
  )
)
